# 12V_PWR.net
KiCad netlist of a schematic drawn in Altium Designer
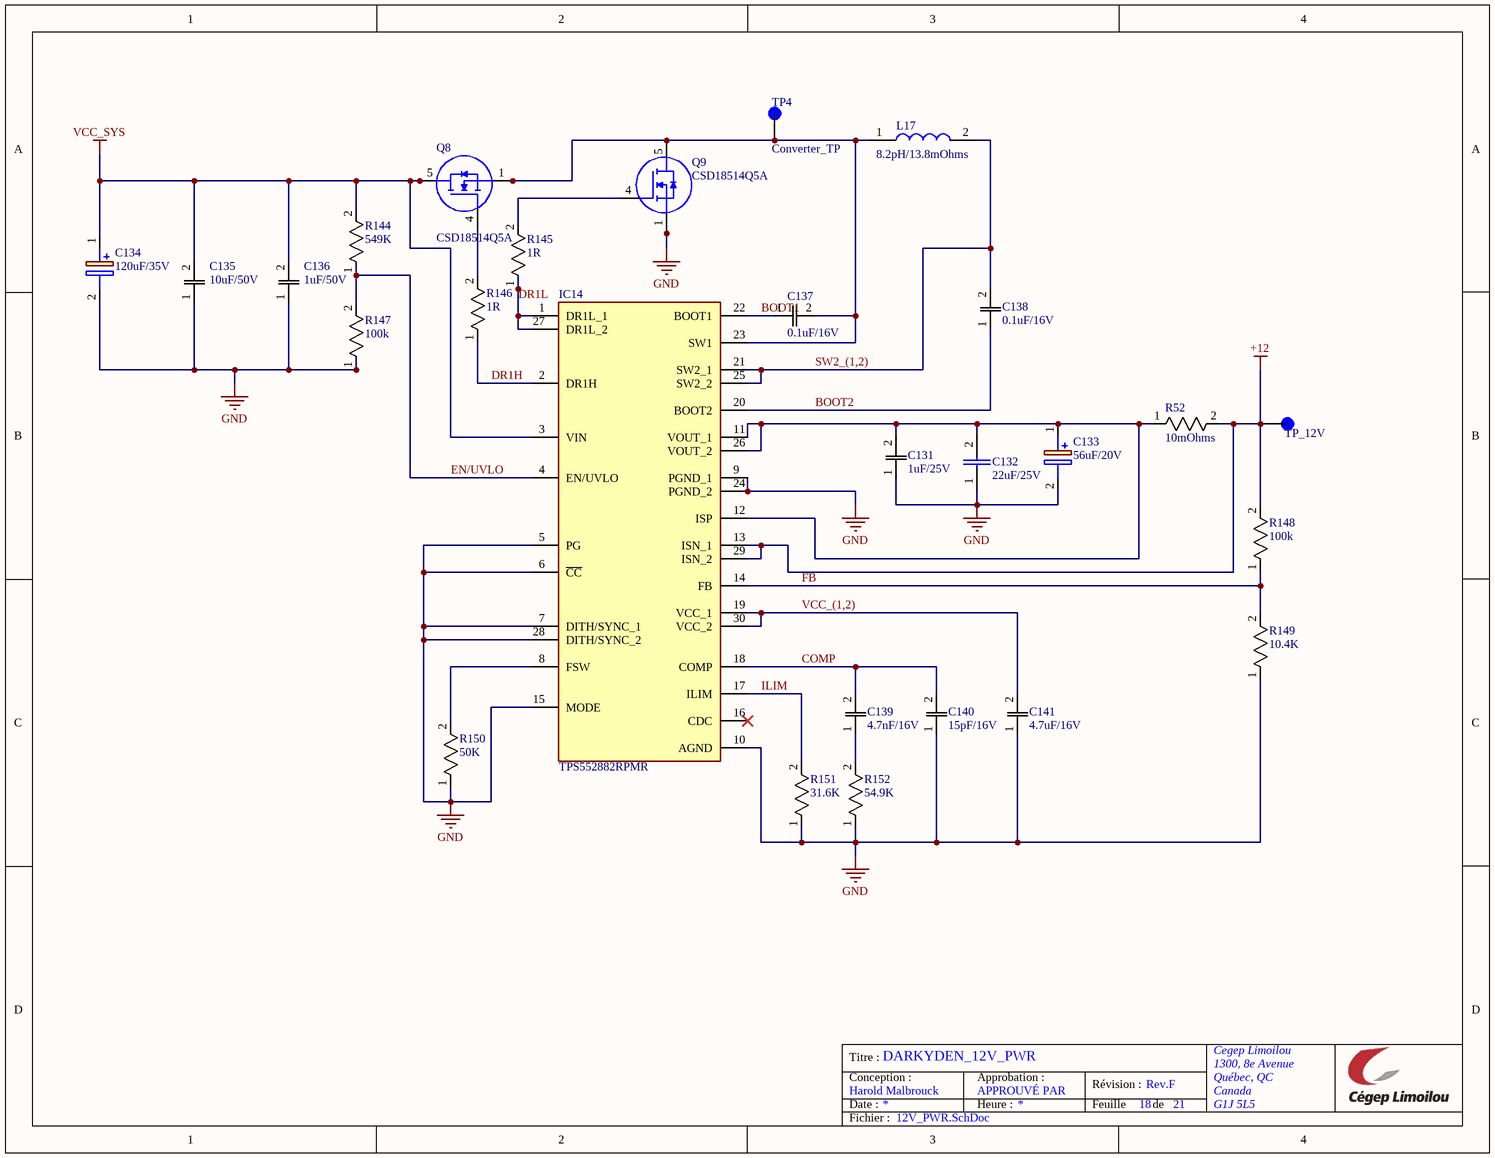
[diagram p0: 12V_PWR.SchDoc]

(export (version "E")
  (design (tool "Eeschema 10.0.6"))
  (components
    (comp (ref "C131")
      (value "1uF/25V")
      (footprint "C0805")
      (description "1 µF, 25 V (DC), ±10 %, SMD 0805, X7R, C0805C105K3RAC7800")
      (fields
        (field (name "MOUSER PART NUMBER") "80-C0805C105K3R")
        (field (name "ARROW PART NUMBER") "C0805C105K3RACTU")
      )
      (libsource (lib "DARKYDEN") (part "C0805C105K3RACTU"))
    )
    (comp (ref "C132")
      (value "22uF/25V")
      (footprint "SamacSys:CAPC3225X270N")
      (description "1210 22 uF 25 V ±10% Tolerance X5R SMT Multilayer Ceramic Capacitor")
      (fields
        (field (name "MOUSER PART NUMBER") "81-GRM32ER61E226KE15")
        (field (name "ARROW PART NUMBER") "GRM32ER61E226KE15L")
      )
      (libsource (lib "SamacSys") (part "GRM32ER61E226KE15L"))
    )
    (comp (ref "C133")
      (value "56uF/20V")
      (footprint "SamacSys:16SVF82M")
      (description "56uF 20VDC 20%( Cap Aluminum Polymer SMD 0.03 Ohm 2800mA 5000h 105C T/R 20SVPF56MX")
      (fields
        (field (name "MOUSER PART NUMBER") "667-20SVPF56MX")
        (field (name "ARROW PART NUMBER") "20SVPF56MX")
      )
      (libsource (lib "SamacSys") (part "20SVPF56MX"))
    )
    (comp (ref "C134")
      (value "120uF/35V")
      (footprint "SamacSys:16SVF1000M")
      (description "120uF 35VDC 20% Cap Aluminum Polymer   SMD 0.018 Ohm 4400mA 5000h 105C T/R")
      (fields
        (field (name "MOUSER PART NUMBER") "667-35SVPF120M")
        (field (name "ARROW PART NUMBER") "35SVPF120M")
      )
      (libsource (lib "SamacSys") (part "35SVPF120M"))
    )
    (comp (ref "C135")
      (value "10uF/50V")
      (footprint "SamacSys:CAPC3225X230N")
      (description "10 uF 50 V 1210 ±20 % Tolerance X7R SMT Multilayer Ceramic Capacitor")
      (fields
        (field (name "MOUSER PART NUMBER") "810-C3225X7R1H106MAC")
        (field (name "ARROW PART NUMBER") "C3225X7R1H106M250AC")
      )
      (libsource (lib "SamacSys") (part "C3225X7R1H106M250AC"))
    )
    (comp (ref "C136")
      (value "1uF/50V")
      (footprint "SamacSys:CAPC1608X80N")
      (description "1uF / 50 V, X5R,  Surface Mount, 0603")
      (fields
        (field (name "MOUSER PART NUMBER") "810-C1608X5R1H105K")
        (field (name "ARROW PART NUMBER") "C1608X5R1H105K080AB")
      )
      (libsource (lib "SamacSys") (part "C1608X5R1H105K080AB"))
    )
    (comp (ref "C137")
      (value "0.1uF/16V")
      (footprint "C0805")
      (description "0.1uF/16V ±10% X7R 0805 (2012METRIC) Ceramic Capacitor SMD Auto X7R")
      (fields
        (field (name "MANUFACTURER") "KEMET")
        (field (name "MANUFACTURER PART NUMBER") "C0805C104K5RACTU")
      )
      (libsource (lib "DARKYDEN") (part "C0805C104K4RACAUTO"))
    )
    (comp (ref "C138")
      (value "0.1uF/16V")
      (footprint "C0805")
      (description "0.1uF/16V ±10% X7R 0805 (2012METRIC) Ceramic Capacitor SMD Auto X7R")
      (fields
        (field (name "MANUFACTURER") "KEMET")
        (field (name "MANUFACTURER PART NUMBER") "C0805C104K5RACTU")
      )
      (libsource (lib "DARKYDEN") (part "C0805C104K4RACAUTO"))
    )
    (comp (ref "C139")
      (value "4.7nF/16V")
      (footprint "c0805")
      (description "4.7nF, 16VDC, 10-% Tol, 10+% Tol, X7R-TC Code, -15, 15%-TC RoHS Compliant: Yes")
      (fields
        (field (name "MANUFACTURER") "KEMET")
        (field (name "MANUFACTURER PART NUMBER") "C0805C472K4RACTU")
      )
      (libsource (lib "DARKYDEN") (part "C0805C472K4RACTU"))
    )
    (comp (ref "C140")
      (value "15pF/16V")
      (footprint "C0805")
      (description "15 pF, 16 V, ± 10%, C0G (NP0), 0805 [2012 Metric]")
      (fields
        (field (name "MANUFACTURER") "KEMET")
        (field (name "MANUFACTURER PART NUMBER") "C0805C150K5RACAUTO")
      )
      (libsource (lib "DARKYDEN") (part "C0805C150K4GACTU"))
    )
    (comp (ref "C141")
      (value "4.7uF/16V")
      (footprint "C0805")
      (description "4.7 uF, 16 V, ± 10%, X7R, 0805 [2012 Metric]")
      (fields
        (field (name "MOUSER PART NUMBER") "80-C0805C475K4R")
        (field (name "ARROW PART NUMBER") "C0805C475K4RACTU")
      )
      (libsource (lib "DARKYDEN") (part "C0805C475K4RACTU"))
    )
    (comp (ref "IC14")
      (value "TPS552882RPMR")
      (footprint "SamacSys:TPS552882RPMR")
      (description "36-V, 16-A buck-boost converter 26-VQFN-HR -40 to 125")
      (fields
        (field (name "MOUSER PART NUMBER") "595-TPS552882RPMR")
        (field (name "MANUFACTURER") "Texas Instruments")
      )
      (libsource (lib "SamacSys") (part "TPS552882RPMR"))
    )
    (comp (ref "L17")
      (value "8.2pH/13.8mOhms")
      (footprint "SamacSys:INDPM135126X650N")
      (description "Inductor Power Shielded/Molded Wirewound 8.2uH 20% 100KHz 15A 0.0138Ohm DCR Automotive T/R")
      (fields
        (field (name "MOUSER PART NUMBER") "673-PA4343.822ANLT")
        (field (name "ARROW PART NUMBER") "PA4343.822ANLT")
      )
      (libsource (lib "SamacSys") (part "PA4343.822ANLT"))
    )
    (comp (ref "Q8")
      (value "CSD18514Q5A")
      (footprint "SamacSys:CSD18514Q5A")
      (description "MOSFET N-Channel 40 V 89A (Tc) 74W (Tc) Surface Mount 8-VSONP (5x6)")
      (fields (field (name "MOUSER PART NUMBER") "595-CSD18514Q5A"))
      (libsource (lib "SamacSys") (part "CSD18514Q5A"))
    )
    (comp (ref "Q9")
      (value "CSD18514Q5A")
      (footprint "SamacSys:CSD18514Q5A")
      (description "MOSFET N-Channel 40 V 89A (Tc) 74W (Tc) Surface Mount 8-VSONP (5x6)")
      (fields (field (name "MOUSER PART NUMBER") "595-CSD18514Q5A"))
      (libsource (lib "SamacSys") (part "CSD18514Q5A"))
    )
    (comp (ref "R52")
      (value "10mOhms")
      (footprint "SamacSys:RESC1608X55N")
      (description "10 Milliohm, ± 5%, 250 mW, 0603 [1608 Metric], Thick Film, High Power")
      (fields
        (field (name "MOUSER PART NUMBER") "667-ERJ-3LWJR010V")
        (field (name "ARROW PART NUMBER") "ERJ-3LWJR010V")
      )
      (libsource (lib "DARKYDEN") (part "ERJ-3LWJR010V"))
    )
    (comp (ref "R144")
      (value "549K")
      (footprint "RESC1608X55N")
      (description "549 kOhm, ± 1%, 100 mW, 0603 [1608 Metric], Thick Film, Precision")
      (fields
        (field (name "MANUFACTURER") "Panasonic")
        (field (name "MANUFACTURER PART NUMBER") "ERJ-3EKF5493V")
      )
      (libsource (lib "DARKYDEN") (part "ERJ-3EKF5493V"))
    )
    (comp (ref "R145")
      (value "1R")
      (footprint "SamacSys:RESC1608X55N")
      (description "1 Ohm 5% 1/10W  Res Thick Film 0603 -100ppm/¦¦")
      (fields
        (field (name "MOUSER PART NUMBER") "667-ERJ-3GEYJ1R0V")
        (field (name "MANUFACTURER") "Panasonic")
      )
      (libsource (lib "DARKYDEN") (part "ERJ-3GEYJ1R0V"))
    )
    (comp (ref "R146")
      (value "1R")
      (footprint "SamacSys:RESC1608X55N")
      (description "1 Ohm 5% 1/10W  Res Thick Film 0603 -100ppm/¦¦")
      (fields
        (field (name "MOUSER PART NUMBER") "667-ERJ-3GEYJ1R0V")
        (field (name "MANUFACTURER") "Panasonic")
      )
      (libsource (lib "DARKYDEN") (part "ERJ-3GEYJ1R0V"))
    )
    (comp (ref "R147")
      (value "100k")
      (footprint "SamacSys:RESC1608X55N")
      (description "100K Ohm 5%  Res Thick Film 0603 1/10W +/-200ppm/ßC Molded SMD Punched Carrier T/R")
      (fields
        (field (name "MOUSER PART NUMBER") "667-ERJ-3GEYJ104V")
        (field (name "ARROW PART NUMBER") "ERJ-3GEYJ104V")
      )
      (libsource (lib "DARKYDEN") (part "ERJ-3GEYJ104V"))
    )
    (comp (ref "R148")
      (value "100k")
      (footprint "SamacSys:RESC1608X55N")
      (description "100K Ohm 5%  Res Thick Film 0603 1/10W +/-200ppm/ßC Molded SMD Punched Carrier T/R")
      (fields
        (field (name "MOUSER PART NUMBER") "667-ERJ-3GEYJ104V")
        (field (name "ARROW PART NUMBER") "ERJ-3GEYJ104V")
      )
      (libsource (lib "DARKYDEN") (part "ERJ-3GEYJ104V"))
    )
    (comp (ref "R149")
      (value "10.4K")
      (footprint "RESC1608X55N")
      (description "10.4kOhm 0.1% High Precision-High Stability Chip Resistor Thin Film 0603  Paper T/R")
      (fields (field (name "MP") "RT0603BRD0710K4L") (field (name "MANUFACTURER") "Yageo"))
      (libsource (lib "DARKYDEN") (part "RT0603BRD0710K4L"))
    )
    (comp (ref "R150")
      (value "50K")
      (footprint "SamacSys:RESC1005X40N")
      (description "50 kΩ  Tolerance: 1.0%  Power: 63 mW  Package:0402")
      (fields
        (field (name "MOUSER PART NUMBER") "71-CRCW0402-50K-E3")
        (field (name "MANUFACTURER PART NUMBER") "CRCW040250K0FKED")
      )
      (libsource (lib "SamacSys") (part "CRCW040250K0FKED"))
    )
    (comp (ref "R151")
      (value "31.6K")
      (footprint "SamacSys:RESC1005X40N")
      (description "31.6 kΩ  Tolerance: 1.0%  Power: 63 mW")
      (fields
        (field (name "MOUSER PART NUMBER") "71-CRCW0402-31.6K-E3")
        (field (name "MANUFACTURER PART NUMBER") "CRCW040231K6FKED")
      )
      (libsource (lib "SamacSys") (part "CRCW040231K6FKED"))
    )
    (comp (ref "R152")
      (value "54.9K")
      (footprint "SamacSys:RESC1005X40N")
      (description "54.9 kΩ  Tolerance: 1.0%  Power: 63 mW  PAckage:0402")
      (fields
        (field (name "MOUSER PART NUMBER") "71-CRCW0402-54.9K-E3")
        (field (name "ARROW PART NUMBER") "CRCW040254K9FKED")
      )
      (libsource (lib "SamacSys") (part "CRCW040254K9FKED"))
    )
    (comp (ref "TP4")
      (value "Converter_TP")
      (footprint "KEYSTONE_5006")
      (description "Test Point Compact THM PC .350 L .125 OD Heat Resistant Nylon 46 Black ¦ Keystone Electronics 5006")
      (fields (field (name "MF") "Keystone Electronics Corp.") (field (name "MP") "5006"))
      (libsource (lib "test_point") (part "5006"))
    )
    (comp (ref "TP_12V")
      (value "~")
      (footprint "KEYSTONE_5006")
      (description "Test Point Compact THM PC .350 L .125 OD Heat Resistant Nylon 46 Black ¦ Keystone Electronics 5006")
      (fields (field (name "MF") "Keystone Electronics Corp.") (field (name "MP") "5006"))
      (libsource (lib "DARKYDEN") (part "5006"))
    )
  )
  (nets
    (net (code "1") (name "+12") (class "Default")
      (node (ref "IC14") (pin "13") (pinfunction "ISN_1_13") (pintype "passive"))
      (node (ref "IC14") (pin "29") (pinfunction "ISN_2_29") (pintype "passive"))
      (node (ref "R148") (pin "2") (pinfunction "2_2") (pintype "passive"))
      (node (ref "R52") (pin "2") (pinfunction "2_2") (pintype "passive"))
      (node (ref "TP_12V") (pin "TP") (pinfunction "TP_TP") (pintype "passive"))
    )
    (net (code "2") (name "/BOOT1") (class "Default")
      (node (ref "C137") (pin "1") (pinfunction "1_1") (pintype "passive"))
      (node (ref "IC14") (pin "22") (pinfunction "BOOT1_22") (pintype "passive"))
    )
    (net (code "3") (name "/BOOT2") (class "Default")
      (node (ref "C138") (pin "1") (pinfunction "1_1") (pintype "passive"))
      (node (ref "IC14") (pin "20") (pinfunction "BOOT2_20") (pintype "passive"))
    )
    (net (code "4") (name "/COMP") (class "Default")
      (node (ref "C139") (pin "2") (pinfunction "2_2") (pintype "passive"))
      (node (ref "C140") (pin "2") (pinfunction "2_2") (pintype "passive"))
      (node (ref "IC14") (pin "18") (pinfunction "COMP_18") (pintype "passive"))
    )
    (net (code "5") (name "/DR1H") (class "Default")
      (node (ref "IC14") (pin "2") (pinfunction "DR1H_2") (pintype "passive"))
      (node (ref "R146") (pin "1") (pinfunction "1_1") (pintype "passive"))
    )
    (net (code "6") (name "/DR1L") (class "Default")
      (node (ref "IC14") (pin "1") (pinfunction "DR1L_1_1") (pintype "passive"))
      (node (ref "IC14") (pin "27") (pinfunction "DR1L_2_27") (pintype "passive"))
      (node (ref "R145") (pin "1") (pinfunction "1_1") (pintype "passive"))
    )
    (net (code "7") (name "/EN{slash}UVLO") (class "Default")
      (node (ref "IC14") (pin "4") (pinfunction "EN/UVLO_4") (pintype "passive"))
      (node (ref "R144") (pin "1") (pinfunction "1_1") (pintype "passive"))
      (node (ref "R147") (pin "2") (pinfunction "2_2") (pintype "passive"))
    )
    (net (code "8") (name "/FB") (class "Default")
      (node (ref "IC14") (pin "14") (pinfunction "FB_14") (pintype "passive"))
      (node (ref "R148") (pin "1") (pinfunction "1_1") (pintype "passive"))
      (node (ref "R149") (pin "2") (pinfunction "2_2") (pintype "passive"))
    )
    (net (code "9") (name "/ILIM") (class "Default")
      (node (ref "IC14") (pin "17") (pinfunction "ILIM_17") (pintype "passive"))
      (node (ref "R151") (pin "2") (pinfunction "2_2") (pintype "passive"))
    )
    (net (code "10") (name "/SW2_(1,2)") (class "Default")
      (node (ref "C138") (pin "2") (pinfunction "2_2") (pintype "passive"))
      (node (ref "IC14") (pin "21") (pinfunction "SW2_1_21") (pintype "passive"))
      (node (ref "IC14") (pin "25") (pinfunction "SW2_2_25") (pintype "passive"))
      (node (ref "L17") (pin "2") (pinfunction "2_2") (pintype "passive"))
    )
    (net (code "11") (name "/VCC_(1,2)") (class "Default")
      (node (ref "C141") (pin "2") (pinfunction "2_2") (pintype "passive"))
      (node (ref "IC14") (pin "19") (pinfunction "VCC_1_19") (pintype "passive"))
      (node (ref "IC14") (pin "30") (pinfunction "VCC_2_30") (pintype "passive"))
    )
    (net (code "12") (name "GND") (class "Default")
      (node (ref "C131") (pin "1") (pinfunction "1_1") (pintype "passive"))
      (node (ref "C132") (pin "1") (pinfunction "1_1") (pintype "passive"))
      (node (ref "C133") (pin "2") (pinfunction "-_2") (pintype "passive"))
      (node (ref "C134") (pin "2") (pinfunction "-_2") (pintype "passive"))
      (node (ref "C135") (pin "1") (pinfunction "1_1") (pintype "passive"))
      (node (ref "C136") (pin "1") (pinfunction "1_1") (pintype "passive"))
      (node (ref "C140") (pin "1") (pinfunction "1_1") (pintype "passive"))
      (node (ref "C141") (pin "1") (pinfunction "1_1") (pintype "passive"))
      (node (ref "IC14") (pin "10") (pinfunction "AGND_10") (pintype "passive"))
      (node (ref "IC14") (pin "15") (pinfunction "MODE_15") (pintype "passive"))
      (node (ref "IC14") (pin "24") (pinfunction "PGND_2_24") (pintype "passive"))
      (node (ref "IC14") (pin "28") (pinfunction "DITH/SYNC_2_28") (pintype "passive"))
      (node (ref "IC14") (pin "5") (pinfunction "PG_5") (pintype "passive"))
      (node (ref "IC14") (pin "6") (pinfunction "~{CC}_6") (pintype "passive"))
      (node (ref "IC14") (pin "7") (pinfunction "DITH/SYNC_1_7") (pintype "passive"))
      (node (ref "IC14") (pin "9") (pinfunction "PGND_1_9") (pintype "passive"))
      (node (ref "Q9") (pin "1") (pinfunction "S_1") (pintype "passive"))
      (node (ref "Q9") (pin "2") (pinfunction "S_2_2") (pintype "passive"))
      (node (ref "Q9") (pin "3") (pinfunction "S_3_3") (pintype "passive"))
      (node (ref "R147") (pin "1") (pinfunction "1_1") (pintype "passive"))
      (node (ref "R149") (pin "1") (pinfunction "1_1") (pintype "passive"))
      (node (ref "R150") (pin "1") (pinfunction "1_1") (pintype "passive"))
      (node (ref "R151") (pin "1") (pinfunction "1_1") (pintype "passive"))
      (node (ref "R152") (pin "1") (pinfunction "1_1") (pintype "passive"))
    )
    (net (code "13") (name "Net-(C133-+)") (class "Default")
      (node (ref "C131") (pin "2") (pinfunction "2_2") (pintype "passive"))
      (node (ref "C132") (pin "2") (pinfunction "2_2") (pintype "passive"))
      (node (ref "C133") (pin "1") (pinfunction "+_1") (pintype "passive"))
      (node (ref "IC14") (pin "11") (pinfunction "VOUT_1_11") (pintype "passive"))
      (node (ref "IC14") (pin "12") (pinfunction "ISP_12") (pintype "passive"))
      (node (ref "IC14") (pin "26") (pinfunction "VOUT_2_26") (pintype "passive"))
      (node (ref "R52") (pin "1") (pinfunction "1_1") (pintype "passive"))
    )
    (net (code "14") (name "Net-(C139-Pad1)") (class "Default")
      (node (ref "C139") (pin "1") (pinfunction "1_1") (pintype "passive"))
      (node (ref "R152") (pin "2") (pinfunction "2_2") (pintype "passive"))
    )
    (net (code "15") (name "Net-(IC14-FSW)") (class "Default")
      (node (ref "IC14") (pin "8") (pinfunction "FSW_8") (pintype "passive"))
      (node (ref "R150") (pin "2") (pinfunction "2_2") (pintype "passive"))
    )
    (net (code "16") (name "Net-(IC14-SW1)") (class "Default")
      (node (ref "C137") (pin "2") (pinfunction "2_2") (pintype "passive"))
      (node (ref "IC14") (pin "23") (pinfunction "SW1_23") (pintype "passive"))
      (node (ref "L17") (pin "1") (pinfunction "1_1") (pintype "passive"))
      (node (ref "Q8") (pin "1") (pinfunction "S_1") (pintype "passive"))
      (node (ref "Q8") (pin "2") (pinfunction "S_2_2") (pintype "passive"))
      (node (ref "Q8") (pin "3") (pinfunction "S_3_3") (pintype "passive"))
      (node (ref "Q9") (pin "5") (pinfunction "D_5") (pintype "passive"))
      (node (ref "Q9") (pin "6") (pinfunction "D_2_6") (pintype "passive"))
      (node (ref "Q9") (pin "7") (pinfunction "D_3_7") (pintype "passive"))
      (node (ref "Q9") (pin "8") (pinfunction "D_4_8") (pintype "passive"))
      (node (ref "Q9") (pin "9") (pinfunction "D_5_9") (pintype "passive"))
      (node (ref "TP4") (pin "TP") (pinfunction "TP_TP") (pintype "passive"))
    )
    (net (code "17") (name "Net-(Q8-G)") (class "Default")
      (node (ref "Q8") (pin "4") (pinfunction "G_4") (pintype "passive"))
      (node (ref "R146") (pin "2") (pinfunction "2_2") (pintype "passive"))
    )
    (net (code "18") (name "Net-(Q9-G)") (class "Default")
      (node (ref "Q9") (pin "4") (pinfunction "G_4") (pintype "passive"))
      (node (ref "R145") (pin "2") (pinfunction "2_2") (pintype "passive"))
    )
    (net (code "19") (name "VCC_SYS") (class "Default")
      (node (ref "C134") (pin "1") (pinfunction "+_1") (pintype "passive"))
      (node (ref "C135") (pin "2") (pinfunction "2_2") (pintype "passive"))
      (node (ref "C136") (pin "2") (pinfunction "2_2") (pintype "passive"))
      (node (ref "IC14") (pin "3") (pinfunction "VIN_3") (pintype "passive"))
      (node (ref "Q8") (pin "5") (pinfunction "D_5") (pintype "passive"))
      (node (ref "Q8") (pin "6") (pinfunction "D_2_6") (pintype "passive"))
      (node (ref "Q8") (pin "7") (pinfunction "D_3_7") (pintype "passive"))
      (node (ref "Q8") (pin "8") (pinfunction "D_4_8") (pintype "passive"))
      (node (ref "Q8") (pin "9") (pinfunction "D_5_9") (pintype "passive"))
      (node (ref "R144") (pin "2") (pinfunction "2_2") (pintype "passive"))
    )
    (net (code "20") (name "unconnected-(IC14-CDC-Pad16)") (class "Default")
      (node (ref "IC14") (pin "16") (pinfunction "CDC_16") (pintype "passive+no_connect"))
    )
  )
)
